# digital_ruler__new.net
KiCad netlist of a schematic drawn in Altium Designer
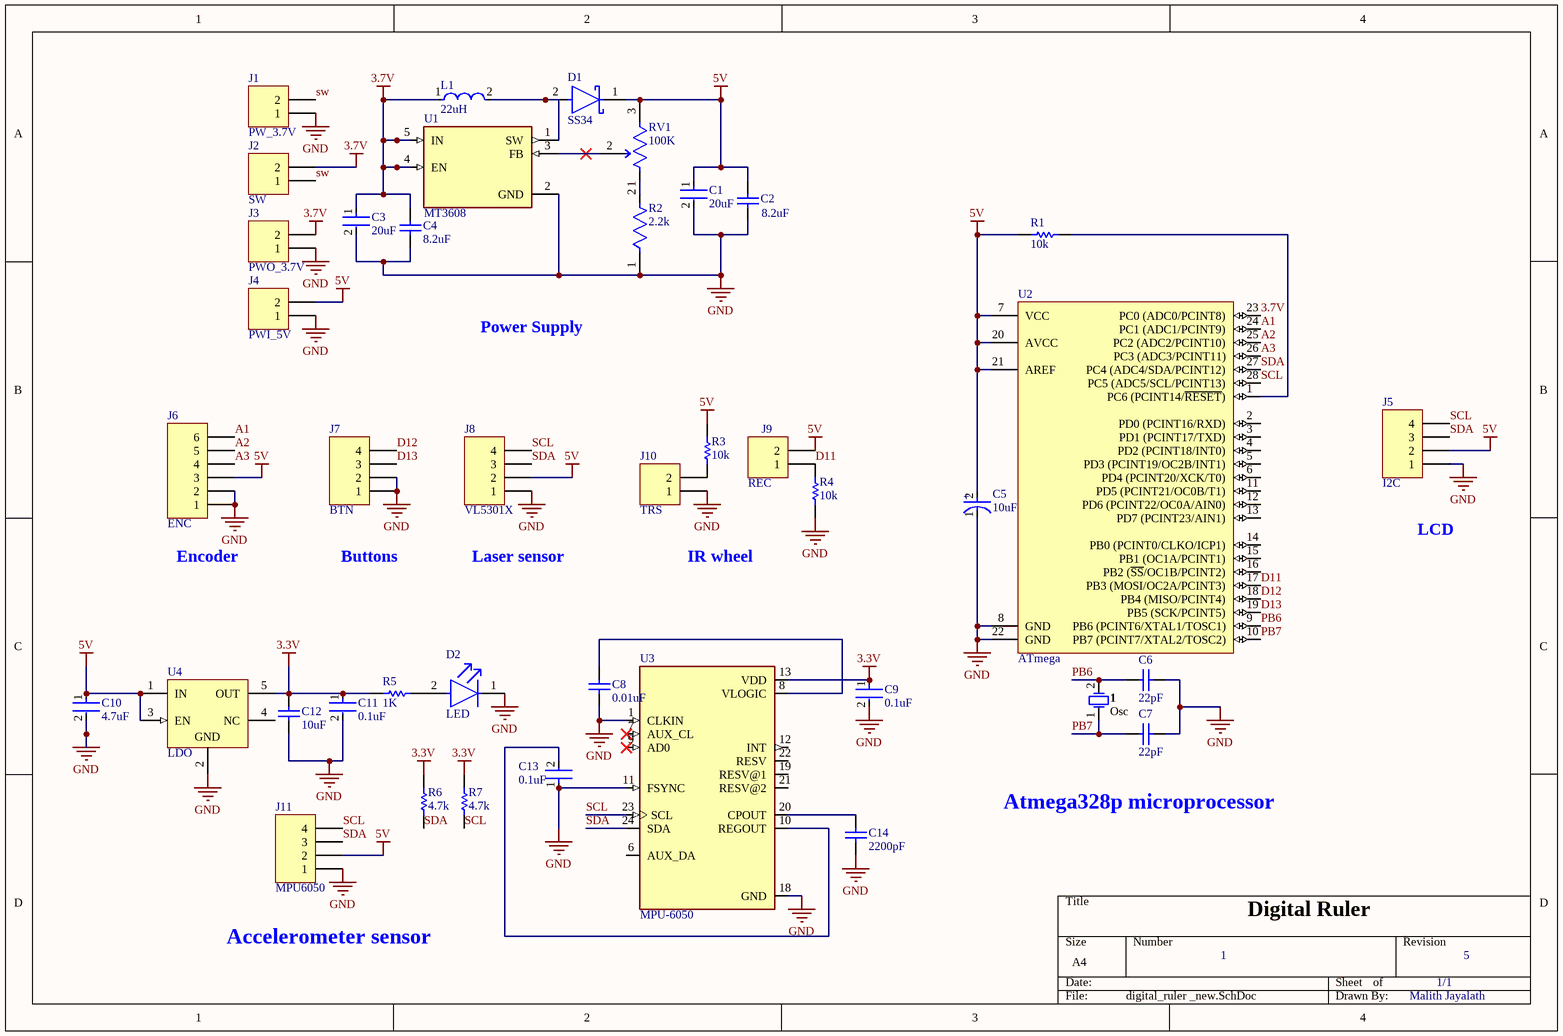
[diagram p0: digital_ruler _new.SchDoc]

(export (version "E")
  (design (tool "Eeschema 10.0.6"))
  (components
    (comp (ref "1")
      (value "Osc")
      (footprint "FOX-FOXSLF160-20")
      (description "Resistance Weld Thru-Hole Crystal, 16 MHz, -20 to 70 degC, 2-Pin THD, RoHS, Bulk")
      (fields (field (name "TOLERANCE") "1%"))
      (libsource (lib "Altium Content Vault") (part "XTAL-1-2-2"))
    )
    (comp (ref "C1")
      (value "20uF")
      (footprint "FP-GRMJN7-0_1-IPC_C")
      (description "Chip Multilayer Ceramic Capacitors for General Purpose, 0704, 20uF, X5R, 15%, 20%, 16V")
      (libsource (lib "Altium Content Vault") (part "02cd4be3c70576c341d710602a673aa"))
    )
    (comp (ref "C2")
      (value "8.2uF")
      (footprint "CAPC1206(3216)190_N")
      (description "CAP 8.2uF 16V ±20% 1206 (3216 Metric) Thickness 1.9mm SMD")
      (fields (field (name "TOLERANCE") "Â±20%"))
      (libsource (lib "Altium Content Vault") (part "CAP"))
    )
    (comp (ref "C3")
      (value "20uF")
      (footprint "FP-GRMJN7-0_1-IPC_C")
      (description "Chip Multilayer Ceramic Capacitors for General Purpose, 0704, 20uF, X5R, 15%, 20%, 16V")
      (libsource (lib "Altium Content Vault") (part "02cd4be3c70576c341d710602a673aa"))
    )
    (comp (ref "C4")
      (value "8.2uF")
      (footprint "CAPC1206(3216)190_N")
      (description "CAP 8.2uF 16V ±20% 1206 (3216 Metric) Thickness 1.9mm SMD")
      (fields (field (name "TOLERANCE") "Â±20%"))
      (libsource (lib "Altium Content Vault") (part "CAP"))
    )
    (comp (ref "C5")
      (value "10uF")
      (footprint "FP-FKC-MFG")
      (description "CAP ALUM 10UF 20% 50V SMD")
      (fields (field (name "TOLERANCE") "20%") (field (name "VOLTAGE") "50V"))
      (libsource (lib "Altium Content Vault") (part "a00bbbee19879c290e62620ae7e47b1"))
    )
    (comp (ref "C6")
      (value "22pF")
      (footprint "CAPC1608X90X35ML10T15")
      (description "Chip Capacitor, 22 pF, +/- 5%, 50 V, -55 to 125 degC, 0603 (1608 Metric), RoHS, Tape and Reel")
      (fields (field (name "MANUFACTURER") "Murata"))
      (libsource (lib "Altium Content Vault") (part "CAP-NP-2"))
    )
    (comp (ref "C7")
      (value "22pF")
      (footprint "CAPC1608X90X35ML10T15")
      (description "Chip Capacitor, 22 pF, +/- 5%, 50 V, -55 to 125 degC, 0603 (1608 Metric), RoHS, Tape and Reel")
      (fields (field (name "MANUFACTURER") "Murata"))
      (libsource (lib "Altium Content Vault") (part "CAP-NP-2"))
    )
    (comp (ref "C8")
      (value "0.01uF")
      (footprint "CAPC1608X90X35ML10T15")
      (description "Chip Capacitor, 10 nF, +/- 10%, 50 V, -55 to 125 degC, 0603 (1608 Metric), RoHS, Tape and Reel")
      (fields (field (name "VOLTAGE") "50V") (field (name "TOLERANCE") "10%"))
      (libsource (lib "Altium Content Vault") (part "CAP-NP-2"))
    )
    (comp (ref "C9")
      (value "0.1uF")
      (footprint "FP-CGA6P-IPC_A")
      (description "Cap Ceramic 100nF 250V X7R 10% Pad SMD 1210 +125°C Automotive T/R")
      (fields (field (name "TOLERANCE") "10%"))
      (libsource (lib "Altium Content Vault") (part "b4654b650e69147ec39a6b967a45e02"))
    )
    (comp (ref "C10")
      (value "4.7uF")
      (footprint "FP-CL10-IPC_A")
      (description "Cap Ceramic 4.7uF 6.3V X6S ±10% Pad SMD 0603 +105°C T/R")
      (fields (field (name "TOLERANCE") "10%"))
      (libsource (lib "Altium Content Vault") (part "b4654b650e69147ec39a6b967a45e02"))
    )
    (comp (ref "C11")
      (value "0.1uF")
      (footprint "FP-CGA6P-IPC_A")
      (description "Cap Ceramic 100nF 250V X7R 10% Pad SMD 1210 +125°C Automotive T/R")
      (fields (field (name "TOLERANCE") "10%"))
      (libsource (lib "Altium Content Vault") (part "b4654b650e69147ec39a6b967a45e02"))
    )
    (comp (ref "C12")
      (value "10uF")
      (footprint "CAPC2013X95X50LL10T25")
      (description "Chip Capacitor, 10 uF, +/- 10%, 6.3 V, -55 to 85 degC, 0805 (2012 Metric), RoHS, Tape and Reel")
      (fields (field (name "TOLERANCE") "±10%") (field (name "MANUFACTURER") "Taiyo Yuden"))
      (libsource (lib "Altium Content Vault") (part "CAP-NP-2"))
    )
    (comp (ref "C13")
      (value "0.1uF")
      (footprint "FP-CGA6P-IPC_A")
      (description "Cap Ceramic 100nF 250V X7R 10% Pad SMD 1210 +125°C Automotive T/R")
      (fields (field (name "TOLERANCE") "10%"))
      (libsource (lib "Altium Content Vault") (part "b4654b650e69147ec39a6b967a45e02"))
    )
    (comp (ref "C14")
      (value "2200pF")
      (footprint "CAPC1608X90X35NL10T15")
      (description "Chip Capacitor, 2.2 nF, +/- 10%, 50 V, -55 to 125 degC, 0603 (1608 Metric), RoHS, Tape and Reel")
      (fields (field (name "MANUFACTURER") "Murata"))
      (libsource (lib "") (part "CAP-NP-2_1"))
    )
    (comp (ref "D1")
      (value "SS34")
      (footprint "FP-95402-MFG")
      (description "DIODE SCHOTTKY 40V 3A DO214AB")
      (fields (field (name "MANUFACTURER") "Vishay") (field (name "MANUFACTURER PART NUMBER") "SS34-E3/57T"))
      (libsource (lib "Altium Content Vault") (part "1d6ec82d83fb6aee721767c19dac4b9"))
    )
    (comp (ref "D2")
      (value "LED")
      (footprint "FP-LTST-C193TBKT-5A-MFG")
      (description "LED BLUE CLEAR CHIP SMD")
      (libsource (lib "Altium Content Vault") (part "8706943c75ba83719d021d2fdc84c58"))
    )
    (comp (ref "J1")
      (value "PW_3.7V")
      (footprint "HDR1X2")
      (description "Header, 2-Pin")
      (fields (field (name "PUBLISHER") "Altium Limited"))
      (libsource (lib "Miscellaneous Connectors") (part "Header 2"))
    )
    (comp (ref "J2")
      (value "SW")
      (footprint "HDR1X2")
      (description "Header, 2-Pin")
      (fields (field (name "PUBLISHER") "Altium Limited"))
      (libsource (lib "Miscellaneous Connectors") (part "Header 2"))
    )
    (comp (ref "J3")
      (value "PWO_3.7V")
      (footprint "HDR1X2")
      (description "Header, 2-Pin")
      (fields (field (name "PUBLISHER") "Altium Limited"))
      (libsource (lib "Miscellaneous Connectors") (part "Header 2"))
    )
    (comp (ref "J4")
      (value "PWI_5V")
      (footprint "HDR1X2")
      (description "Header, 2-Pin")
      (fields (field (name "PUBLISHER") "Altium Limited"))
      (libsource (lib "Miscellaneous Connectors") (part "Header 2"))
    )
    (comp (ref "J5")
      (value "I2C")
      (footprint "HDR1X4")
      (description "Header, 4-Pin")
      (fields (field (name "PUBLISHER") "Altium Limited"))
      (libsource (lib "Miscellaneous Connectors") (part "Header 4"))
    )
    (comp (ref "J6")
      (value "ENC")
      (footprint "HDR1X6")
      (description "Header, 6-Pin")
      (fields (field (name "PUBLISHER") "Altium Limited"))
      (libsource (lib "Miscellaneous Connectors") (part "Header 6"))
    )
    (comp (ref "J7")
      (value "BTN")
      (footprint "HDR1X4")
      (description "Header, 4-Pin")
      (fields (field (name "PUBLISHER") "Altium Limited"))
      (libsource (lib "Miscellaneous Connectors") (part "Header 4"))
    )
    (comp (ref "J8")
      (value "VL5301X")
      (footprint "HDR1X4")
      (description "Header, 4-Pin")
      (fields (field (name "PUBLISHER") "Altium Limited"))
      (libsource (lib "Miscellaneous Connectors") (part "Header 4"))
    )
    (comp (ref "J9")
      (value "REC")
      (footprint "HDR1X2")
      (description "Header, 2-Pin")
      (fields (field (name "PUBLISHER") "Altium Limited"))
      (libsource (lib "Miscellaneous Connectors") (part "Header 2"))
    )
    (comp (ref "J10")
      (value "TRS")
      (footprint "HDR1X2")
      (description "Header, 2-Pin")
      (fields (field (name "PUBLISHER") "Altium Limited"))
      (libsource (lib "Miscellaneous Connectors") (part "Header 2"))
    )
    (comp (ref "J11")
      (value "MPU6050")
      (footprint "HDR1X4")
      (description "Header, 4-Pin")
      (fields (field (name "PUBLISHER") "Altium Limited"))
      (libsource (lib "Miscellaneous Connectors") (part "Header 4"))
    )
    (comp (ref "L1")
      (value "22uH")
      (footprint "FP-IHLP-2525CZ-FP_2_413x3-MFG")
      (description "Commercial Inductors, Low DCR Series 22uH 2.9A 135mΩ 20%")
      (fields (field (name "TOLERANCE") "20%"))
      (libsource (lib "Altium Content Vault") (part "725321dda6339637d4d059423bc1c3c"))
    )
    (comp (ref "R1")
      (value "10k")
      (footprint "RESC1005X40X25ML05T05")
      (fields (field (name "PART NUMBER") "ERJ-2GEJ103X") (field (name "MANUFACTURER") "Panasonic"))
      (libsource (lib "Altium Content Vault") (part "RES"))
    )
    (comp (ref "R2")
      (value "2.2k")
      (footprint "FP-ERA2A-MFG")
      (description "RES SMD 2.2K OHM 0.1% 1/16W 0402")
      (fields (field (name "TOLERANCE") "0.1%") (field (name "MANUFACTURER PART NUMBER") "ERA-2AEB222X"))
      (libsource (lib "Altium Content Vault") (part "1029c3af85768c4190bb7ad29bc67b5"))
    )
    (comp (ref "R3")
      (value "10k")
      (footprint "RESC1005X40X25ML05T05")
      (fields (field (name "PART NUMBER") "ERJ-2GEJ103X") (field (name "MANUFACTURER") "Panasonic"))
      (libsource (lib "Altium Content Vault") (part "RES"))
    )
    (comp (ref "R4")
      (value "10k")
      (footprint "RESC1005X40X25ML05T05")
      (fields (field (name "PART NUMBER") "ERJ-2GEJ103X") (field (name "MANUFACTURER") "Panasonic"))
      (libsource (lib "Altium Content Vault") (part "RES"))
    )
    (comp (ref "R5")
      (value "1K")
      (footprint "RESC2013X60X35ML10T20")
      (description "Chip Resistor, 1 KOhm, +/- 1%, 125 mW, -55 to 155 degC, 0805 (2012 Metric), RoHS, Tape and Reel")
      (fields (field (name "TOLERANCE") "1%") (field (name "MANUFACTURER") "Yageo"))
      (libsource (lib "Altium Content Vault") (part "RES-2"))
    )
    (comp (ref "R6")
      (value "4.7k")
      (footprint "RESC2013X70X40NL20T20")
      (description "Chip Resistor, 4.7 KOhm, +/- 1%, 0.125 W, -55 to 155 degC, 0805 (2012 Metric), RoHS, Tape and Reel")
      (fields (field (name "MANUFACTURER") "Panasonic"))
      (libsource (lib "Altium Content Vault") (part "RES-2"))
    )
    (comp (ref "R7")
      (value "4.7k")
      (footprint "RESC2013X70X40NL20T20")
      (description "Chip Resistor, 4.7 KOhm, +/- 1%, 0.125 W, -55 to 155 degC, 0805 (2012 Metric), RoHS, Tape and Reel")
      (fields (field (name "MANUFACTURER") "Panasonic"))
      (libsource (lib "Altium Content Vault") (part "RES-2"))
    )
    (comp (ref "RV1")
      (value "100K")
      (footprint "FP-3386P-MFG")
      (description "TRIMMER 100K OHM 0.5W PC PIN TOP")
      (fields (field (name "TOLERANCE") "10%"))
      (libsource (lib "Altium Content Vault") (part "13357d81287629c2fd191d242cfa50c"))
    )
    (comp (ref "U1")
      (value "MT3608")
      (footprint "MT3608:SOT95P280X145-6N")
      (description "High Efficiency 1.2MHz 2A Step Up Converter")
      (fields (field (name "MF") "{'manufacturer': u'Aerosemi Technology Co., Ltd'}"))
      (libsource (lib "*") (part "MT3608"))
    )
    (comp (ref "U2")
      (value "ATmega")
      (footprint "28P3")
      (libsource (lib "Altium Content Vault") (part "MC-8B-ATM48-IL28"))
    )
    (comp (ref "U3")
      (value "MPU-6050")
      (footprint "MPU-6050:QFN50P400X400X95-24N")
      (description "MPU-6050 Six-Axis (Gyro + Accelerometer) MEMS MotionTrackingâ„¢ Devices")
      (fields (field (name "MF") "{'manufacturer': u'TDK InvenSense'}"))
      (libsource (lib "*") (part "MPU-6050"))
    )
    (comp (ref "U4")
      (value "LDO")
      (footprint "DBV0005A_M")
      (fields (field (name "PARTNUMBER") "TPS76133DBVT") (field (name "MANUFACTURER") "Texas Instruments"))
      (libsource (lib "Altium Content Vault") (part "TI-TXX7XXXX-5"))
    )
  )
  (nets
    (net (code "1") (name "/A1") (class "Default")
      (node (ref "J6") (pin "6") (pinfunction "6_6") (pintype "passive"))
      (node (ref "U2") (pin "24") (pinfunction "PC1_(ADC1/PCINT9)_24") (pintype "bidirectional"))
    )
    (net (code "2") (name "/A2") (class "Default")
      (node (ref "J6") (pin "5") (pinfunction "5_5") (pintype "passive"))
      (node (ref "U2") (pin "25") (pinfunction "PC2_(ADC2/PCINT10)_25") (pintype "bidirectional"))
    )
    (net (code "3") (name "/A3") (class "Default")
      (node (ref "J6") (pin "4") (pinfunction "4_4") (pintype "passive"))
      (node (ref "U2") (pin "26") (pinfunction "PC3_(ADC3/PCINT11)_26") (pintype "bidirectional"))
    )
    (net (code "4") (name "/D11") (class "Default")
      (node (ref "J9") (pin "1") (pinfunction "1_1") (pintype "passive"))
      (node (ref "R4") (pin "2") (pinfunction "2_2") (pintype "passive"))
      (node (ref "U2") (pin "17") (pinfunction "PB3_(MOSI/OC2A/PCINT3)_17") (pintype "bidirectional"))
    )
    (net (code "5") (name "/D12") (class "Default")
      (node (ref "J7") (pin "4") (pinfunction "4_4") (pintype "passive"))
      (node (ref "U2") (pin "18") (pinfunction "PB4_(MISO/PCINT4)_18") (pintype "bidirectional"))
    )
    (net (code "6") (name "/D13") (class "Default")
      (node (ref "J7") (pin "3") (pinfunction "3_3") (pintype "passive"))
      (node (ref "U2") (pin "19") (pinfunction "PB5_(SCK/PCINT5)_19") (pintype "bidirectional"))
    )
    (net (code "7") (name "/PB6") (class "Default")
      (node (ref "1") (pin "2") (pinfunction "2_2") (pintype "passive"))
      (node (ref "C6") (pin "2") (pinfunction "2_2") (pintype "passive"))
      (node (ref "U2") (pin "9") (pinfunction "PB6_(PCINT6/XTAL1/TOSC1)_9") (pintype "bidirectional"))
    )
    (net (code "8") (name "/PB7") (class "Default")
      (node (ref "1") (pin "1") (pinfunction "1_1") (pintype "passive"))
      (node (ref "C7") (pin "2") (pinfunction "2_2") (pintype "passive"))
      (node (ref "U2") (pin "10") (pinfunction "PB7_(PCINT7/XTAL2/TOSC2)_10") (pintype "bidirectional"))
    )
    (net (code "9") (name "/SCL") (class "Default")
      (node (ref "J11") (pin "4") (pinfunction "4_4") (pintype "passive"))
      (node (ref "J5") (pin "4") (pinfunction "4_4") (pintype "passive"))
      (node (ref "J8") (pin "4") (pinfunction "4_4") (pintype "passive"))
      (node (ref "R7") (pin "2") (pinfunction "2_2") (pintype "passive"))
      (node (ref "U2") (pin "28") (pinfunction "PC5_(ADC5/SCL/PCINT13)_28") (pintype "bidirectional"))
      (node (ref "U3") (pin "23") (pinfunction "SCL_23") (pintype "input"))
    )
    (net (code "10") (name "/SDA") (class "Default")
      (node (ref "J11") (pin "3") (pinfunction "3_3") (pintype "passive"))
      (node (ref "J5") (pin "3") (pinfunction "3_3") (pintype "passive"))
      (node (ref "J8") (pin "3") (pinfunction "3_3") (pintype "passive"))
      (node (ref "R6") (pin "2") (pinfunction "2_2") (pintype "passive"))
      (node (ref "U2") (pin "27") (pinfunction "PC4_(ADC4/SDA/PCINT12)_27") (pintype "bidirectional"))
      (node (ref "U3") (pin "24") (pinfunction "SDA_24") (pintype "bidirectional"))
    )
    (net (code "11") (name "/sw") (class "Default")
      (node (ref "J1") (pin "2") (pinfunction "2_2") (pintype "passive"))
      (node (ref "J2") (pin "1") (pinfunction "1_1") (pintype "passive"))
    )
    (net (code "12") (name "3.3V") (class "Default")
      (node (ref "C11") (pin "1") (pinfunction "1_1") (pintype "passive"))
      (node (ref "C12") (pin "2") (pinfunction "2_2") (pintype "passive"))
      (node (ref "C9") (pin "1") (pinfunction "1_1") (pintype "passive"))
      (node (ref "R5") (pin "1") (pinfunction "1_1") (pintype "passive"))
      (node (ref "R6") (pin "1") (pinfunction "1_1") (pintype "passive"))
      (node (ref "R7") (pin "1") (pinfunction "1_1") (pintype "passive"))
      (node (ref "U3") (pin "13") (pinfunction "VDD_13") (pintype "power_in"))
      (node (ref "U4") (pin "5") (pinfunction "OUT_5") (pintype "power_in"))
    )
    (net (code "13") (name "3.7V") (class "Default")
      (node (ref "C3") (pin "1") (pinfunction "1_1") (pintype "passive"))
      (node (ref "C4") (pin "2") (pinfunction "2_2") (pintype "passive"))
      (node (ref "J2") (pin "2") (pinfunction "2_2") (pintype "passive"))
      (node (ref "J3") (pin "2") (pinfunction "2_2") (pintype "passive"))
      (node (ref "L1") (pin "1") (pinfunction "1_1") (pintype "passive"))
      (node (ref "U1") (pin "4") (pinfunction "EN_4") (pintype "input"))
      (node (ref "U1") (pin "5") (pinfunction "IN_5") (pintype "input"))
      (node (ref "U2") (pin "23") (pinfunction "PC0_(ADC0/PCINT8)_23") (pintype "bidirectional"))
    )
    (net (code "14") (name "5V") (class "Default")
      (node (ref "C1") (pin "1") (pinfunction "1_1") (pintype "passive"))
      (node (ref "C10") (pin "1") (pinfunction "1_1") (pintype "passive"))
      (node (ref "C2") (pin "2") (pinfunction "2_2") (pintype "passive"))
      (node (ref "C5") (pin "2") (pinfunction "A_2") (pintype "passive"))
      (node (ref "D1") (pin "1") (pinfunction "C_1") (pintype "passive"))
      (node (ref "J11") (pin "2") (pinfunction "2_2") (pintype "passive"))
      (node (ref "J4") (pin "2") (pinfunction "2_2") (pintype "passive"))
      (node (ref "J5") (pin "2") (pinfunction "2_2") (pintype "passive"))
      (node (ref "J6") (pin "3") (pinfunction "3_3") (pintype "passive"))
      (node (ref "J8") (pin "2") (pinfunction "2_2") (pintype "passive"))
      (node (ref "J9") (pin "2") (pinfunction "2_2") (pintype "passive"))
      (node (ref "R1") (pin "1") (pinfunction "1_1") (pintype "passive"))
      (node (ref "R3") (pin "1") (pinfunction "1_1") (pintype "passive"))
      (node (ref "RV1") (pin "3") (pinfunction "CW_3") (pintype "passive"))
      (node (ref "U2") (pin "20") (pinfunction "AVCC_20") (pintype "power_in"))
      (node (ref "U2") (pin "21") (pinfunction "AREF_21") (pintype "power_in"))
      (node (ref "U2") (pin "7") (pinfunction "VCC_7") (pintype "power_in"))
      (node (ref "U4") (pin "1") (pinfunction "IN_1") (pintype "power_in"))
      (node (ref "U4") (pin "3") (pinfunction "EN_3") (pintype "input"))
    )
    (net (code "15") (name "GND") (class "Default")
      (node (ref "C1") (pin "2") (pinfunction "2_2") (pintype "passive"))
      (node (ref "C10") (pin "2") (pinfunction "2_2") (pintype "passive"))
      (node (ref "C11") (pin "2") (pinfunction "2_2") (pintype "passive"))
      (node (ref "C12") (pin "1") (pinfunction "1_1") (pintype "passive"))
      (node (ref "C13") (pin "1") (pinfunction "1_1") (pintype "passive"))
      (node (ref "C14") (pin "1") (pinfunction "1_1") (pintype "passive"))
      (node (ref "C2") (pin "1") (pinfunction "1_1") (pintype "passive"))
      (node (ref "C3") (pin "2") (pinfunction "2_2") (pintype "passive"))
      (node (ref "C4") (pin "1") (pinfunction "1_1") (pintype "passive"))
      (node (ref "C5") (pin "1") (pinfunction "C_1") (pintype "passive"))
      (node (ref "C6") (pin "1") (pinfunction "1_1") (pintype "passive"))
      (node (ref "C7") (pin "1") (pinfunction "1_1") (pintype "passive"))
      (node (ref "C8") (pin "1") (pinfunction "1_1") (pintype "passive"))
      (node (ref "C9") (pin "2") (pinfunction "2_2") (pintype "passive"))
      (node (ref "D2") (pin "1") (pinfunction "C_1") (pintype "passive"))
      (node (ref "J1") (pin "1") (pinfunction "1_1") (pintype "passive"))
      (node (ref "J10") (pin "1") (pinfunction "1_1") (pintype "passive"))
      (node (ref "J11") (pin "1") (pinfunction "1_1") (pintype "passive"))
      (node (ref "J3") (pin "1") (pinfunction "1_1") (pintype "passive"))
      (node (ref "J4") (pin "1") (pinfunction "1_1") (pintype "passive"))
      (node (ref "J5") (pin "1") (pinfunction "1_1") (pintype "passive"))
      (node (ref "J6") (pin "1") (pinfunction "1_1") (pintype "passive"))
      (node (ref "J6") (pin "2") (pinfunction "2_2") (pintype "passive"))
      (node (ref "J7") (pin "1") (pinfunction "1_1") (pintype "passive"))
      (node (ref "J7") (pin "2") (pinfunction "2_2") (pintype "passive"))
      (node (ref "J8") (pin "1") (pinfunction "1_1") (pintype "passive"))
      (node (ref "R2") (pin "1") (pinfunction "1_1") (pintype "passive"))
      (node (ref "R4") (pin "1") (pinfunction "1_1") (pintype "passive"))
      (node (ref "U1") (pin "2") (pinfunction "GND_2") (pintype "power_in"))
      (node (ref "U2") (pin "22") (pinfunction "GND_22") (pintype "power_in"))
      (node (ref "U2") (pin "8") (pinfunction "GND_8") (pintype "power_in"))
      (node (ref "U3") (pin "1") (pinfunction "CLKIN_1") (pintype "input"))
      (node (ref "U3") (pin "11") (pinfunction "FSYNC_11") (pintype "input"))
      (node (ref "U3") (pin "18") (pinfunction "GND_18") (pintype "power_in"))
      (node (ref "U4") (pin "2") (pinfunction "GND_2") (pintype "power_in"))
    )
    (net (code "16") (name "Net-(D1-A)") (class "Default")
      (node (ref "D1") (pin "2") (pinfunction "A_2") (pintype "passive"))
      (node (ref "L1") (pin "2") (pinfunction "2_2") (pintype "passive"))
      (node (ref "U1") (pin "1") (pinfunction "SW_1") (pintype "output"))
    )
    (net (code "17") (name "Net-(D2-A)") (class "Default")
      (node (ref "D2") (pin "2") (pinfunction "A_2") (pintype "passive"))
      (node (ref "R5") (pin "2") (pinfunction "2_2") (pintype "passive"))
    )
    (net (code "18") (name "Net-(J10-Pad2)") (class "Default")
      (node (ref "J10") (pin "2") (pinfunction "2_2") (pintype "passive"))
      (node (ref "R3") (pin "2") (pinfunction "2_2") (pintype "passive"))
    )
    (net (code "19") (name "Net-(RV1-CCW)") (class "Default")
      (node (ref "R2") (pin "2") (pinfunction "2_2") (pintype "passive"))
      (node (ref "RV1") (pin "1") (pinfunction "CCW_1") (pintype "passive"))
    )
    (net (code "20") (name "Net-(RV1-WIPER)") (class "Default")
      (node (ref "RV1") (pin "2") (pinfunction "WIPER_2") (pintype "passive"))
      (node (ref "U1") (pin "3") (pinfunction "FB_3") (pintype "input"))
    )
    (net (code "21") (name "Net-(U2-PC6_(PCINT14{slash}~{RESET}))") (class "Default")
      (node (ref "R1") (pin "2") (pinfunction "2_2") (pintype "passive"))
      (node (ref "U2") (pin "1") (pinfunction "PC6_(PCINT14/~{RESET})_1") (pintype "bidirectional"))
    )
    (net (code "22") (name "Net-(U3-CPOUT)") (class "Default")
      (node (ref "C14") (pin "2") (pinfunction "2_2") (pintype "passive"))
      (node (ref "U3") (pin "20") (pinfunction "CPOUT_20") (pintype "passive"))
    )
    (net (code "23") (name "Net-(U3-REGOUT)") (class "Default")
      (node (ref "C13") (pin "2") (pinfunction "2_2") (pintype "passive"))
      (node (ref "U3") (pin "10") (pinfunction "REGOUT_10") (pintype "passive"))
    )
    (net (code "24") (name "Net-(U3-VLOGIC)") (class "Default")
      (node (ref "C8") (pin "2") (pinfunction "2_2") (pintype "passive"))
      (node (ref "U3") (pin "8") (pinfunction "VLOGIC_8") (pintype "power_in"))
    )
    (net (code "25") (name "unconnected-(U2-PB0_(PCINT0{slash}CLKO{slash}ICP1)-Pad14)") (class "Default")
      (node (ref "U2") (pin "14") (pinfunction "PB0_(PCINT0/CLKO/ICP1)_14") (pintype "bidirectional"))
    )
    (net (code "26") (name "unconnected-(U2-PB1_(OC1A{slash}PCINT1)-Pad15)") (class "Default")
      (node (ref "U2") (pin "15") (pinfunction "PB1_(OC1A/PCINT1)_15") (pintype "bidirectional"))
    )
    (net (code "27") (name "unconnected-(U2-PB2_(~{SS}{slash}OC1B{slash}PCINT2)-Pad16)") (class "Default")
      (node (ref "U2") (pin "16") (pinfunction "PB2_(~{SS}/OC1B/PCINT2)_16") (pintype "bidirectional"))
    )
    (net (code "28") (name "unconnected-(U2-PD0_(PCINT16{slash}RXD)-Pad2)") (class "Default")
      (node (ref "U2") (pin "2") (pinfunction "PD0_(PCINT16/RXD)_2") (pintype "bidirectional"))
    )
    (net (code "29") (name "unconnected-(U2-PD1_(PCINT17{slash}TXD)-Pad3)") (class "Default")
      (node (ref "U2") (pin "3") (pinfunction "PD1_(PCINT17/TXD)_3") (pintype "bidirectional"))
    )
    (net (code "30") (name "unconnected-(U2-PD2_(PCINT18{slash}INT0)-Pad4)") (class "Default")
      (node (ref "U2") (pin "4") (pinfunction "PD2_(PCINT18/INT0)_4") (pintype "bidirectional"))
    )
    (net (code "31") (name "unconnected-(U2-PD3_(PCINT19{slash}OC2B{slash}INT1)-Pad5)") (class "Default")
      (node (ref "U2") (pin "5") (pinfunction "PD3_(PCINT19/OC2B/INT1)_5") (pintype "bidirectional"))
    )
    (net (code "32") (name "unconnected-(U2-PD4_(PCINT20{slash}XCK{slash}T0)-Pad6)") (class "Default")
      (node (ref "U2") (pin "6") (pinfunction "PD4_(PCINT20/XCK/T0)_6") (pintype "bidirectional"))
    )
    (net (code "33") (name "unconnected-(U2-PD5_(PCINT21{slash}OC0B{slash}T1)-Pad11)") (class "Default")
      (node (ref "U2") (pin "11") (pinfunction "PD5_(PCINT21/OC0B/T1)_11") (pintype "bidirectional"))
    )
    (net (code "34") (name "unconnected-(U2-PD6_(PCINT22{slash}OC0A{slash}AIN0)-Pad12)") (class "Default")
      (node (ref "U2") (pin "12") (pinfunction "PD6_(PCINT22/OC0A/AIN0)_12") (pintype "bidirectional"))
    )
    (net (code "35") (name "unconnected-(U2-PD7_(PCINT23{slash}AIN1)-Pad13)") (class "Default")
      (node (ref "U2") (pin "13") (pinfunction "PD7_(PCINT23/AIN1)_13") (pintype "bidirectional"))
    )
    (net (code "36") (name "unconnected-(U3-AD0-Pad9)") (class "Default")
      (node (ref "U3") (pin "9") (pinfunction "AD0_9") (pintype "input+no_connect"))
    )
    (net (code "37") (name "unconnected-(U3-AUX_CL-Pad7)") (class "Default")
      (node (ref "U3") (pin "7") (pinfunction "AUX_CL_7") (pintype "input+no_connect"))
    )
    (net (code "38") (name "unconnected-(U3-AUX_DA-Pad6)") (class "Default")
      (node (ref "U3") (pin "6") (pinfunction "AUX_DA_6") (pintype "bidirectional"))
    )
    (net (code "39") (name "unconnected-(U3-INT-Pad12)") (class "Default")
      (node (ref "U3") (pin "12") (pinfunction "INT_12") (pintype "output"))
    )
    (net (code "40") (name "unconnected-(U3-RESV-Pad22)") (class "Default")
      (node (ref "U3") (pin "22") (pinfunction "RESV_22") (pintype "passive"))
    )
    (net (code "41") (name "unconnected-(U3-RESV@1-Pad19)") (class "Default")
      (node (ref "U3") (pin "19") (pinfunction "RESV@1_19") (pintype "passive"))
    )
    (net (code "42") (name "unconnected-(U3-RESV@2-Pad21)") (class "Default")
      (node (ref "U3") (pin "21") (pinfunction "RESV@2_21") (pintype "passive"))
    )
    (net (code "43") (name "unconnected-(U4-NC-Pad4)") (class "Default")
      (node (ref "U4") (pin "4") (pinfunction "NC_4") (pintype "passive"))
    )
  )
)
